# untitled.net
KiCad netlist of a schematic drawn in EAGLE
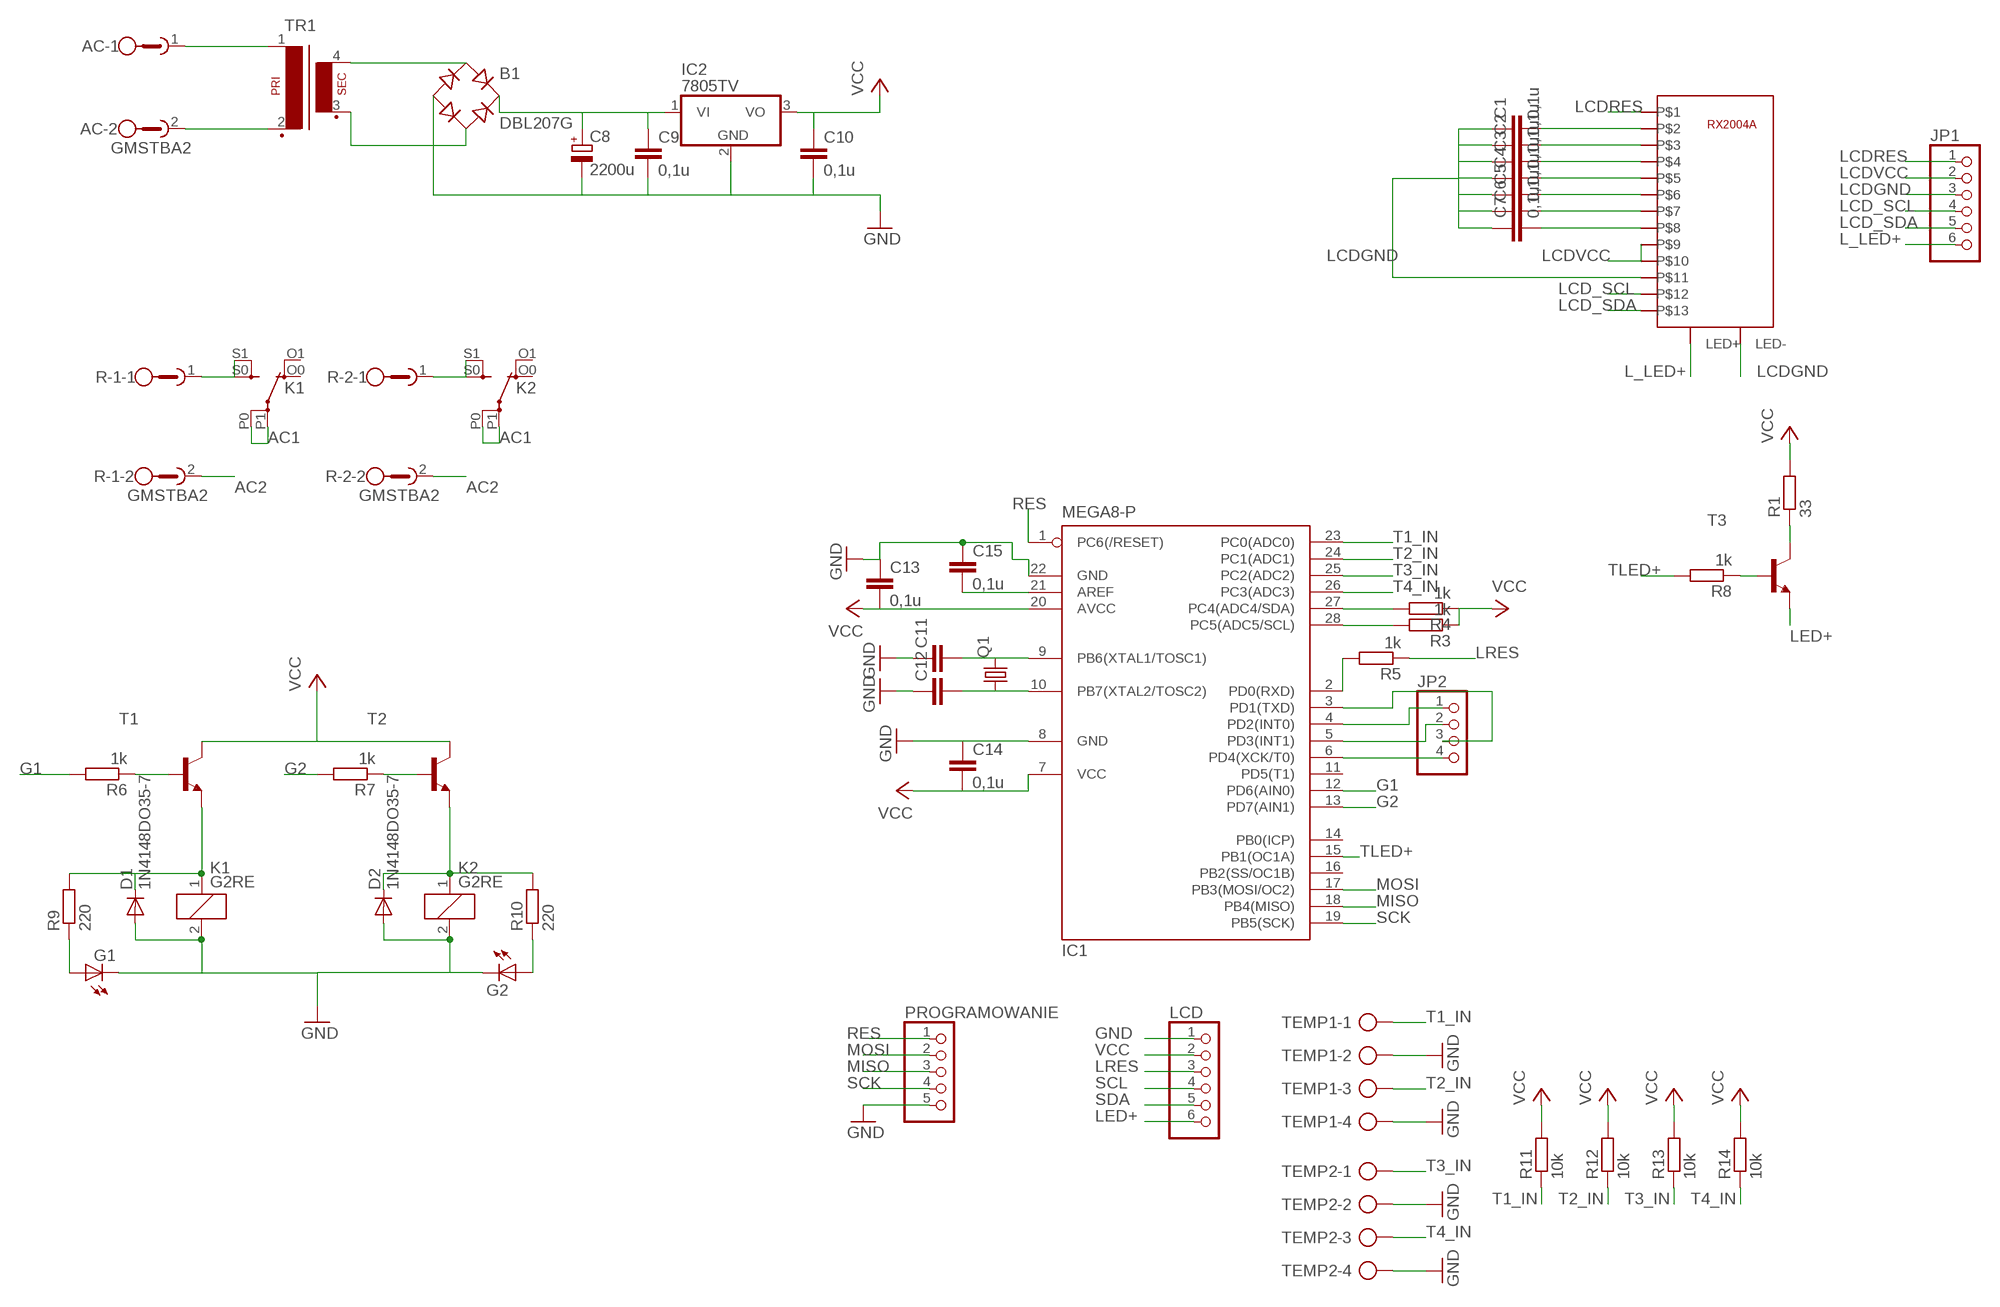
[diagram p0: schematic, sheet 1]

(export (version "E")
  (design (tool "Eeschema 10.0.6"))
  (components
    (comp (ref "AC")
      (value "GMSTBA2")
      (footprint "eagle-import:GMSTBA2")
      (fields (field (name "MF") "FARNELL") (field (name "MPN") "1757242"))
      (libsource (lib "eagle-import") (part "GMSTBA2"))
    )
    (comp (ref "B1")
      (value "DBL207G")
      (footprint "eagle-import:DB")
      (libsource (lib "eagle-import") (part "DB?GL207"))
    )
    (comp (ref "C1")
      (value "0,1u")
      (footprint "eagle-import:C1206K")
      (libsource (lib "eagle-import") (part "C-EUC1206K"))
    )
    (comp (ref "C2")
      (value "0,1u")
      (footprint "eagle-import:C1206K")
      (libsource (lib "eagle-import") (part "C-EUC1206K"))
    )
    (comp (ref "C3")
      (value "0,1u")
      (footprint "eagle-import:C1206K")
      (libsource (lib "eagle-import") (part "C-EUC1206K"))
    )
    (comp (ref "C4")
      (value "0,1u")
      (footprint "eagle-import:C1206K")
      (libsource (lib "eagle-import") (part "C-EUC1206K"))
    )
    (comp (ref "C5")
      (value "0,1u")
      (footprint "eagle-import:C1206K")
      (libsource (lib "eagle-import") (part "C-EUC1206K"))
    )
    (comp (ref "C6")
      (value "0,1u")
      (footprint "eagle-import:C1206K")
      (libsource (lib "eagle-import") (part "C-EUC1206K"))
    )
    (comp (ref "C7")
      (value "0,1u")
      (footprint "eagle-import:C1206K")
      (libsource (lib "eagle-import") (part "C-EUC1206K"))
    )
    (comp (ref "C8")
      (value "2200u")
      (footprint "eagle-import:E7,5-16")
      (libsource (lib "eagle-import") (part "CPOL-EUE7.5-16"))
    )
    (comp (ref "C9")
      (value "0,1u")
      (footprint "eagle-import:C1206K")
      (libsource (lib "eagle-import") (part "C-EUC1206K"))
    )
    (comp (ref "C10")
      (value "0,1u")
      (footprint "eagle-import:C1206K")
      (libsource (lib "eagle-import") (part "C-EUC1206K"))
    )
    (comp (ref "C11")
      (value "C-EU025-024X044")
      (footprint "eagle-import:C025-024X044")
      (libsource (lib "eagle-import") (part "C-EU025-024X044"))
    )
    (comp (ref "C12")
      (value "C-EU025-024X044")
      (footprint "eagle-import:C025-024X044")
      (libsource (lib "eagle-import") (part "C-EU025-024X044"))
    )
    (comp (ref "C13")
      (value "0,1u")
      (footprint "eagle-import:C1206K")
      (libsource (lib "eagle-import") (part "C-EUC1206K"))
    )
    (comp (ref "C14")
      (value "0,1u")
      (footprint "eagle-import:C1206K")
      (libsource (lib "eagle-import") (part "C-EUC1206K"))
    )
    (comp (ref "C15")
      (value "0,1u")
      (footprint "eagle-import:C1206K")
      (libsource (lib "eagle-import") (part "C-EUC1206K"))
    )
    (comp (ref "D1")
      (value "1N4148DO35-7")
      (footprint "eagle-import:DO35-7")
      (libsource (lib "eagle-import") (part "1N4148DO35-7"))
    )
    (comp (ref "D2")
      (value "1N4148DO35-7")
      (footprint "eagle-import:DO35-7")
      (libsource (lib "eagle-import") (part "1N4148DO35-7"))
    )
    (comp (ref "G1")
      (value "LED3MM")
      (footprint "eagle-import:LED3MM")
      (libsource (lib "eagle-import") (part "LED3MM"))
    )
    (comp (ref "G2")
      (value "LED3MM")
      (footprint "eagle-import:LED3MM")
      (libsource (lib "eagle-import") (part "LED3MM"))
    )
    (comp (ref "IC1")
      (value "MEGA8-P")
      (footprint "eagle-import:DIL28-3")
      (libsource (lib "eagle-import") (part "MEGA8-P"))
    )
    (comp (ref "IC2")
      (value "7805TV")
      (footprint "eagle-import:TO220V")
      (libsource (lib "eagle-import") (part "78TV05"))
    )
    (comp (ref "JP1")
      (value "PINHD-1X6/90")
      (footprint "eagle-import:1X06_90")
      (libsource (lib "eagle-import") (part "PINHD-1X6/90"))
    )
    (comp (ref "JP2")
      (value "PINHD-1X4")
      (footprint "eagle-import:1X04")
      (libsource (lib "eagle-import") (part "PINHD-1X4"))
    )
    (comp (ref "K1")
      (value "G2RE")
      (footprint "eagle-import:G2RE")
      (libsource (lib "eagle-import") (part "G2RE"))
    )
    (comp (ref "K2")
      (value "G2RE")
      (footprint "eagle-import:G2RE")
      (libsource (lib "eagle-import") (part "G2RE"))
    )
    (comp (ref "LCD")
      (value "PINHD-1X6")
      (footprint "eagle-import:1X06")
      (libsource (lib "eagle-import") (part "PINHD-1X6"))
    )
    (comp (ref "PROGRAMOWANIE")
      (value "PINHD-1X5")
      (footprint "eagle-import:1X05")
      (libsource (lib "eagle-import") (part "PINHD-1X5"))
    )
    (comp (ref "Q1")
      (value "CRYSTALHC49S")
      (footprint "eagle-import:HC49_S")
      (libsource (lib "eagle-import") (part "CRYSTALHC49S"))
    )
    (comp (ref "R-1")
      (value "GMSTBA2")
      (footprint "eagle-import:GMSTBA2")
      (fields (field (name "MF") "FARNELL") (field (name "MPN") "1757242"))
      (libsource (lib "eagle-import") (part "GMSTBA2"))
    )
    (comp (ref "R-2")
      (value "GMSTBA2")
      (footprint "eagle-import:GMSTBA2")
      (fields (field (name "MF") "FARNELL") (field (name "MPN") "1757242"))
      (libsource (lib "eagle-import") (part "GMSTBA2"))
    )
    (comp (ref "R1")
      (value "33")
      (footprint "eagle-import:0204_7")
      (libsource (lib "eagle-import") (part "R-EU_0204/7"))
    )
    (comp (ref "R3")
      (value "1k")
      (footprint "eagle-import:0204_5")
      (libsource (lib "eagle-import") (part "R-EU_0204/5"))
    )
    (comp (ref "R4")
      (value "1k")
      (footprint "eagle-import:0204_5")
      (libsource (lib "eagle-import") (part "R-EU_0204/5"))
    )
    (comp (ref "R5")
      (value "1k")
      (footprint "eagle-import:0204_7")
      (libsource (lib "eagle-import") (part "R-EU_0204/7"))
    )
    (comp (ref "R6")
      (value "1k")
      (footprint "eagle-import:0204_5")
      (libsource (lib "eagle-import") (part "R-EU_0204/5"))
    )
    (comp (ref "R7")
      (value "1k")
      (footprint "eagle-import:0204_5")
      (libsource (lib "eagle-import") (part "R-EU_0204/5"))
    )
    (comp (ref "R8")
      (value "1k")
      (footprint "eagle-import:0204_5")
      (libsource (lib "eagle-import") (part "R-EU_0204/5"))
    )
    (comp (ref "R9")
      (value "220")
      (footprint "eagle-import:0204_7")
      (libsource (lib "eagle-import") (part "R-EU_0204/7"))
    )
    (comp (ref "R10")
      (value "220")
      (footprint "eagle-import:0204_7")
      (libsource (lib "eagle-import") (part "R-EU_0204/7"))
    )
    (comp (ref "R11")
      (value "10k")
      (footprint "eagle-import:0204_5")
      (libsource (lib "eagle-import") (part "R-EU_0204/5"))
    )
    (comp (ref "R12")
      (value "10k")
      (footprint "eagle-import:0204_5")
      (libsource (lib "eagle-import") (part "R-EU_0204/5"))
    )
    (comp (ref "R13")
      (value "10k")
      (footprint "eagle-import:0204_5")
      (libsource (lib "eagle-import") (part "R-EU_0204/5"))
    )
    (comp (ref "R14")
      (value "10k")
      (footprint "eagle-import:0204_5")
      (libsource (lib "eagle-import") (part "R-EU_0204/5"))
    )
    (comp (ref "T1")
      (value "BC337-NPN-TO92-CBE")
      (footprint "eagle-import:TO92-CBE")
      (libsource (lib "eagle-import") (part "-NPN-TO92-CBEBC337"))
    )
    (comp (ref "T2")
      (value "BC337-NPN-TO92-CBE")
      (footprint "eagle-import:TO92-CBE")
      (libsource (lib "eagle-import") (part "-NPN-TO92-CBEBC337"))
    )
    (comp (ref "T3")
      (value "BC337-NPN-TO92-CBE")
      (footprint "eagle-import:TO92-CBE")
      (libsource (lib "eagle-import") (part "-NPN-TO92-CBEBC337"))
    )
    (comp (ref "TEMP1")
      (value "AK500/4")
      (footprint "eagle-import:AK500_4")
      (libsource (lib "eagle-import") (part "AK500/4"))
    )
    (comp (ref "TEMP2")
      (value "AK500/4")
      (footprint "eagle-import:AK500_4")
      (libsource (lib "eagle-import") (part "AK500/4"))
    )
    (comp (ref "TR1")
      (value "VP31")
      (footprint "eagle-import:VP31")
      (libsource (lib "eagle-import") (part "VP31"))
    )
    (comp (ref "U$1")
      (value "RX2004A")
      (footprint "eagle-import:RX2004A")
      (libsource (lib "eagle-import") (part "RX2004A"))
    )
  )
  (nets
    (net (code "1") (name "/AC1") (class "Default")
      (node (ref "AC") (pin "1") (pinfunction "1_1") (pintype "passive"))
      (node (ref "K1") (pin "P0") (pinfunction "P_P0") (pintype "passive"))
      (node (ref "K1") (pin "P1") (pinfunction "P_P1") (pintype "passive"))
      (node (ref "K2") (pin "P0") (pinfunction "P_P0") (pintype "passive"))
      (node (ref "K2") (pin "P1") (pinfunction "P_P1") (pintype "passive"))
      (node (ref "TR1") (pin "1") (pinfunction "P1_1") (pintype "passive"))
    )
    (net (code "2") (name "/AC2") (class "Default")
      (node (ref "AC") (pin "2") (pinfunction "1_2") (pintype "passive"))
      (node (ref "R-1") (pin "2") (pinfunction "1_2") (pintype "passive"))
      (node (ref "R-2") (pin "2") (pinfunction "1_2") (pintype "passive"))
      (node (ref "TR1") (pin "2") (pinfunction "P2_2") (pintype "passive"))
    )
    (net (code "3") (name "/G1") (class "Default")
      (node (ref "IC1") (pin "12") (pinfunction "PD6(AIN0)_12") (pintype "bidirectional"))
      (node (ref "R6") (pin "2") (pinfunction "2_2") (pintype "passive"))
    )
    (net (code "4") (name "/G2") (class "Default")
      (node (ref "IC1") (pin "13") (pinfunction "PD7(AIN1)_13") (pintype "bidirectional"))
      (node (ref "R7") (pin "2") (pinfunction "2_2") (pintype "passive"))
    )
    (net (code "5") (name "/LCDGND") (class "Default")
      (node (ref "C1") (pin "1") (pinfunction "1_1") (pintype "passive"))
      (node (ref "C2") (pin "1") (pinfunction "1_1") (pintype "passive"))
      (node (ref "C3") (pin "1") (pinfunction "1_1") (pintype "passive"))
      (node (ref "C4") (pin "1") (pinfunction "1_1") (pintype "passive"))
      (node (ref "C5") (pin "1") (pinfunction "1_1") (pintype "passive"))
      (node (ref "C6") (pin "1") (pinfunction "1_1") (pintype "passive"))
      (node (ref "C7") (pin "1") (pinfunction "1_1") (pintype "passive"))
      (node (ref "JP1") (pin "3") (pinfunction "3_3") (pintype "passive"))
      (node (ref "U$1") (pin "LED-") (pinfunction "LED-_LED-") (pintype "bidirectional"))
      (node (ref "U$1") (pin "P$11") (pinfunction "P$11_P$11") (pintype "bidirectional"))
    )
    (net (code "6") (name "/LCDRES") (class "Default")
      (node (ref "JP1") (pin "1") (pinfunction "1_1") (pintype "passive"))
      (node (ref "U$1") (pin "P$1") (pinfunction "P$1_P$1") (pintype "bidirectional"))
    )
    (net (code "7") (name "/LCDVCC") (class "Default")
      (node (ref "JP1") (pin "2") (pinfunction "2_2") (pintype "passive"))
      (node (ref "U$1") (pin "P$10") (pinfunction "P$10_P$10") (pintype "bidirectional"))
      (node (ref "U$1") (pin "P$9") (pinfunction "P$9_P$9") (pintype "bidirectional"))
    )
    (net (code "8") (name "/LCD_SCL") (class "Default")
      (node (ref "JP1") (pin "4") (pinfunction "4_4") (pintype "passive"))
      (node (ref "U$1") (pin "P$12") (pinfunction "P$12_P$12") (pintype "bidirectional"))
    )
    (net (code "9") (name "/LCD_SDA") (class "Default")
      (node (ref "JP1") (pin "5") (pinfunction "5_5") (pintype "passive"))
      (node (ref "U$1") (pin "P$13") (pinfunction "P$13_P$13") (pintype "bidirectional"))
    )
    (net (code "10") (name "/LED+") (class "Default")
      (node (ref "LCD") (pin "6") (pinfunction "6_6") (pintype "passive"))
      (node (ref "T3") (pin "E") (pinfunction "E_E") (pintype "passive"))
    )
    (net (code "11") (name "/LRES") (class "Default")
      (node (ref "LCD") (pin "3") (pinfunction "3_3") (pintype "passive"))
      (node (ref "R5") (pin "1") (pinfunction "1_1") (pintype "passive"))
    )
    (net (code "12") (name "/L_LED+") (class "Default")
      (node (ref "JP1") (pin "6") (pinfunction "6_6") (pintype "passive"))
      (node (ref "U$1") (pin "LED+") (pinfunction "LED+_LED+") (pintype "bidirectional"))
    )
    (net (code "13") (name "/MISO") (class "Default")
      (node (ref "IC1") (pin "18") (pinfunction "PB4(MISO)_18") (pintype "bidirectional"))
      (node (ref "PROGRAMOWANIE") (pin "3") (pinfunction "3_3") (pintype "passive"))
    )
    (net (code "14") (name "/MOSI") (class "Default")
      (node (ref "IC1") (pin "17") (pinfunction "PB3(MOSI/OC2)_17") (pintype "bidirectional"))
      (node (ref "PROGRAMOWANIE") (pin "2") (pinfunction "2_2") (pintype "passive"))
    )
    (net (code "15") (name "/RES") (class "Default")
      (node (ref "IC1") (pin "1") (pinfunction "PC6(/RESET)_1") (pintype "bidirectional"))
      (node (ref "PROGRAMOWANIE") (pin "1") (pinfunction "1_1") (pintype "passive"))
    )
    (net (code "16") (name "/SCK") (class "Default")
      (node (ref "IC1") (pin "19") (pinfunction "PB5(SCK)_19") (pintype "bidirectional"))
      (node (ref "PROGRAMOWANIE") (pin "4") (pinfunction "4_4") (pintype "passive"))
    )
    (net (code "17") (name "/SCL") (class "Default")
      (node (ref "IC1") (pin "28") (pinfunction "PC5(ADC5/SCL)_28") (pintype "bidirectional"))
      (node (ref "LCD") (pin "4") (pinfunction "4_4") (pintype "passive"))
      (node (ref "R3") (pin "2") (pinfunction "2_2") (pintype "passive"))
    )
    (net (code "18") (name "/SDA") (class "Default")
      (node (ref "IC1") (pin "27") (pinfunction "PC4(ADC4/SDA)_27") (pintype "bidirectional"))
      (node (ref "LCD") (pin "5") (pinfunction "5_5") (pintype "passive"))
      (node (ref "R4") (pin "2") (pinfunction "2_2") (pintype "passive"))
    )
    (net (code "19") (name "/T1_IN") (class "Default")
      (node (ref "IC1") (pin "23") (pinfunction "PC0(ADC0)_23") (pintype "bidirectional"))
      (node (ref "R11") (pin "1") (pinfunction "1_1") (pintype "passive"))
      (node (ref "TEMP1") (pin "1") (pinfunction "KL_1") (pintype "passive"))
    )
    (net (code "20") (name "/T2_IN") (class "Default")
      (node (ref "IC1") (pin "24") (pinfunction "PC1(ADC1)_24") (pintype "bidirectional"))
      (node (ref "R12") (pin "1") (pinfunction "1_1") (pintype "passive"))
      (node (ref "TEMP1") (pin "3") (pinfunction "KL_3") (pintype "passive"))
    )
    (net (code "21") (name "/T3_IN") (class "Default")
      (node (ref "IC1") (pin "25") (pinfunction "PC2(ADC2)_25") (pintype "bidirectional"))
      (node (ref "R13") (pin "1") (pinfunction "1_1") (pintype "passive"))
      (node (ref "TEMP2") (pin "1") (pinfunction "KL_1") (pintype "passive"))
    )
    (net (code "22") (name "/T4_IN") (class "Default")
      (node (ref "IC1") (pin "26") (pinfunction "PC3(ADC3)_26") (pintype "bidirectional"))
      (node (ref "R14") (pin "1") (pinfunction "1_1") (pintype "passive"))
      (node (ref "TEMP2") (pin "3") (pinfunction "KL_3") (pintype "passive"))
    )
    (net (code "23") (name "/TLED+") (class "Default")
      (node (ref "IC1") (pin "15") (pinfunction "PB1(OC1A)_15") (pintype "bidirectional"))
      (node (ref "R8") (pin "2") (pinfunction "2_2") (pintype "passive"))
    )
    (net (code "24") (name "GND") (class "Default")
      (node (ref "B1") (pin "-") (pinfunction "-_-") (pintype "passive"))
      (node (ref "C10") (pin "2") (pinfunction "2_2") (pintype "passive"))
      (node (ref "C11") (pin "1") (pinfunction "1_1") (pintype "passive"))
      (node (ref "C12") (pin "1") (pinfunction "1_1") (pintype "passive"))
      (node (ref "C13") (pin "1") (pinfunction "1_1") (pintype "passive"))
      (node (ref "C14") (pin "1") (pinfunction "1_1") (pintype "passive"))
      (node (ref "C15") (pin "1") (pinfunction "1_1") (pintype "passive"))
      (node (ref "C8") (pin "-") (pinfunction "-_-") (pintype "passive"))
      (node (ref "C9") (pin "2") (pinfunction "2_2") (pintype "passive"))
      (node (ref "D1") (pin "A") (pinfunction "A_A") (pintype "passive"))
      (node (ref "D2") (pin "A") (pinfunction "A_A") (pintype "passive"))
      (node (ref "G1") (pin "K") (pinfunction "C_K") (pintype "passive"))
      (node (ref "G2") (pin "K") (pinfunction "C_K") (pintype "passive"))
      (node (ref "IC1") (pin "22") (pinfunction "GND_22") (pintype "power_in"))
      (node (ref "IC1") (pin "8") (pinfunction "GND_8") (pintype "power_in"))
      (node (ref "IC2") (pin "2") (pinfunction "GND_2") (pintype "passive"))
      (node (ref "K1") (pin "2") (pinfunction "2_2") (pintype "passive"))
      (node (ref "K2") (pin "2") (pinfunction "2_2") (pintype "passive"))
      (node (ref "LCD") (pin "1") (pinfunction "1_1") (pintype "passive"))
      (node (ref "PROGRAMOWANIE") (pin "5") (pinfunction "5_5") (pintype "passive"))
      (node (ref "TEMP1") (pin "2") (pinfunction "KL_2") (pintype "passive"))
      (node (ref "TEMP1") (pin "4") (pinfunction "KL_4") (pintype "passive"))
      (node (ref "TEMP2") (pin "2") (pinfunction "KL_2") (pintype "passive"))
      (node (ref "TEMP2") (pin "4") (pinfunction "KL_4") (pintype "passive"))
    )
    (net (code "25") (name "Net-(C1-Pad2)") (class "Default")
      (node (ref "C1") (pin "2") (pinfunction "2_2") (pintype "passive"))
      (node (ref "U$1") (pin "P$2") (pinfunction "P$2_P$2") (pintype "bidirectional"))
    )
    (net (code "26") (name "Net-(C2-Pad2)") (class "Default")
      (node (ref "C2") (pin "2") (pinfunction "2_2") (pintype "passive"))
      (node (ref "U$1") (pin "P$3") (pinfunction "P$3_P$3") (pintype "bidirectional"))
    )
    (net (code "27") (name "Net-(C3-Pad2)") (class "Default")
      (node (ref "C3") (pin "2") (pinfunction "2_2") (pintype "passive"))
      (node (ref "U$1") (pin "P$4") (pinfunction "P$4_P$4") (pintype "bidirectional"))
    )
    (net (code "28") (name "Net-(C4-Pad2)") (class "Default")
      (node (ref "C4") (pin "2") (pinfunction "2_2") (pintype "passive"))
      (node (ref "U$1") (pin "P$5") (pinfunction "P$5_P$5") (pintype "bidirectional"))
    )
    (net (code "29") (name "Net-(C5-Pad2)") (class "Default")
      (node (ref "C5") (pin "2") (pinfunction "2_2") (pintype "passive"))
      (node (ref "U$1") (pin "P$6") (pinfunction "P$6_P$6") (pintype "bidirectional"))
    )
    (net (code "30") (name "Net-(C6-Pad2)") (class "Default")
      (node (ref "C6") (pin "2") (pinfunction "2_2") (pintype "passive"))
      (node (ref "U$1") (pin "P$7") (pinfunction "P$7_P$7") (pintype "bidirectional"))
    )
    (net (code "31") (name "Net-(C7-Pad2)") (class "Default")
      (node (ref "C7") (pin "2") (pinfunction "2_2") (pintype "passive"))
      (node (ref "U$1") (pin "P$8") (pinfunction "P$8_P$8") (pintype "bidirectional"))
    )
    (net (code "32") (name "Net-(D1-PadC)") (class "Default")
      (node (ref "D1") (pin "C") (pinfunction "C_C") (pintype "passive"))
      (node (ref "K1") (pin "1") (pinfunction "1_1") (pintype "passive"))
      (node (ref "R9") (pin "2") (pinfunction "2_2") (pintype "passive"))
      (node (ref "T1") (pin "E") (pinfunction "E_E") (pintype "passive"))
    )
    (net (code "33") (name "Net-(D2-PadC)") (class "Default")
      (node (ref "D2") (pin "C") (pinfunction "C_C") (pintype "passive"))
      (node (ref "K2") (pin "1") (pinfunction "1_1") (pintype "passive"))
      (node (ref "R10") (pin "2") (pinfunction "2_2") (pintype "passive"))
      (node (ref "T2") (pin "E") (pinfunction "E_E") (pintype "passive"))
    )
    (net (code "34") (name "Net-(G1-PadA)") (class "Default")
      (node (ref "G1") (pin "A") (pinfunction "A_A") (pintype "passive"))
      (node (ref "R9") (pin "1") (pinfunction "1_1") (pintype "passive"))
    )
    (net (code "35") (name "Net-(G2-PadA)") (class "Default")
      (node (ref "G2") (pin "A") (pinfunction "A_A") (pintype "passive"))
      (node (ref "R10") (pin "1") (pinfunction "1_1") (pintype "passive"))
    )
    (net (code "36") (name "Net-(IC1-AREF)") (class "Default")
      (node (ref "C15") (pin "2") (pinfunction "2_2") (pintype "passive"))
      (node (ref "IC1") (pin "21") (pinfunction "AREF_21") (pintype "passive"))
    )
    (net (code "37") (name "Net-(IC1-PB6(XTAL1{slash}TOSC1))") (class "Default")
      (node (ref "C11") (pin "2") (pinfunction "2_2") (pintype "passive"))
      (node (ref "IC1") (pin "9") (pinfunction "PB6(XTAL1/TOSC1)_9") (pintype "bidirectional"))
      (node (ref "Q1") (pin "2") (pinfunction "2_2") (pintype "passive"))
    )
    (net (code "38") (name "Net-(IC1-PB7(XTAL2{slash}TOSC2))") (class "Default")
      (node (ref "C12") (pin "2") (pinfunction "2_2") (pintype "passive"))
      (node (ref "IC1") (pin "10") (pinfunction "PB7(XTAL2/TOSC2)_10") (pintype "bidirectional"))
      (node (ref "Q1") (pin "1") (pinfunction "1_1") (pintype "passive"))
    )
    (net (code "39") (name "Net-(IC1-PD0(RXD))") (class "Default")
      (node (ref "IC1") (pin "2") (pinfunction "PD0(RXD)_2") (pintype "bidirectional"))
      (node (ref "R5") (pin "2") (pinfunction "2_2") (pintype "passive"))
    )
    (net (code "40") (name "Net-(IC1-PD1(TXD))") (class "Default")
      (node (ref "IC1") (pin "3") (pinfunction "PD1(TXD)_3") (pintype "bidirectional"))
      (node (ref "JP2") (pin "3") (pinfunction "3_3") (pintype "passive"))
    )
    (net (code "41") (name "Net-(IC1-PD2(INT0))") (class "Default")
      (node (ref "IC1") (pin "4") (pinfunction "PD2(INT0)_4") (pintype "bidirectional"))
      (node (ref "JP2") (pin "1") (pinfunction "1_1") (pintype "passive"))
    )
    (net (code "42") (name "Net-(IC1-PD3(INT1))") (class "Default")
      (node (ref "IC1") (pin "5") (pinfunction "PD3(INT1)_5") (pintype "bidirectional"))
      (node (ref "JP2") (pin "2") (pinfunction "2_2") (pintype "passive"))
    )
    (net (code "43") (name "Net-(IC1-PD4(XCK{slash}T0))") (class "Default")
      (node (ref "IC1") (pin "6") (pinfunction "PD4(XCK/T0)_6") (pintype "bidirectional"))
      (node (ref "JP2") (pin "4") (pinfunction "4_4") (pintype "passive"))
    )
    (net (code "44") (name "Net-(IC2-VI)") (class "Default")
      (node (ref "B1") (pin "+") (pinfunction "+_+") (pintype "passive"))
      (node (ref "C8") (pin "+") (pinfunction "+_+") (pintype "passive"))
      (node (ref "C9") (pin "1") (pinfunction "1_1") (pintype "passive"))
      (node (ref "IC2") (pin "1") (pinfunction "VI_1") (pintype "input"))
    )
    (net (code "45") (name "Net-(K1B-S-PadS0)") (class "Default")
      (node (ref "K1") (pin "S0") (pinfunction "S_S0") (pintype "passive"))
      (node (ref "K1") (pin "S1") (pinfunction "S_S1") (pintype "passive"))
      (node (ref "R-1") (pin "1") (pinfunction "1_1") (pintype "passive"))
    )
    (net (code "46") (name "Net-(K2B-S-PadS0)") (class "Default")
      (node (ref "K2") (pin "S0") (pinfunction "S_S0") (pintype "passive"))
      (node (ref "K2") (pin "S1") (pinfunction "S_S1") (pintype "passive"))
      (node (ref "R-2") (pin "1") (pinfunction "1_1") (pintype "passive"))
    )
    (net (code "47") (name "Net-(R1-Pad1)") (class "Default")
      (node (ref "R1") (pin "1") (pinfunction "1_1") (pintype "passive"))
      (node (ref "T3") (pin "C") (pinfunction "C_C") (pintype "passive"))
    )
    (net (code "48") (name "Net-(R6-Pad1)") (class "Default")
      (node (ref "R6") (pin "1") (pinfunction "1_1") (pintype "passive"))
      (node (ref "T1") (pin "B") (pinfunction "B_B") (pintype "passive"))
    )
    (net (code "49") (name "Net-(R7-Pad1)") (class "Default")
      (node (ref "R7") (pin "1") (pinfunction "1_1") (pintype "passive"))
      (node (ref "T2") (pin "B") (pinfunction "B_B") (pintype "passive"))
    )
    (net (code "50") (name "Net-(R8-Pad1)") (class "Default")
      (node (ref "R8") (pin "1") (pinfunction "1_1") (pintype "passive"))
      (node (ref "T3") (pin "B") (pinfunction "B_B") (pintype "passive"))
    )
    (net (code "51") (name "Net-(TR1-S3)") (class "Default")
      (node (ref "B1") (pin "AC2") (pinfunction "AC2_AC2") (pintype "passive"))
      (node (ref "TR1") (pin "3") (pinfunction "S3_3") (pintype "passive"))
    )
    (net (code "52") (name "Net-(TR1-S4)") (class "Default")
      (node (ref "B1") (pin "AC1") (pinfunction "AC1_AC1") (pintype "passive"))
      (node (ref "TR1") (pin "4") (pinfunction "S4_4") (pintype "passive"))
    )
    (net (code "53") (name "VCC") (class "Default")
      (node (ref "C10") (pin "1") (pinfunction "1_1") (pintype "passive"))
      (node (ref "C13") (pin "2") (pinfunction "2_2") (pintype "passive"))
      (node (ref "C14") (pin "2") (pinfunction "2_2") (pintype "passive"))
      (node (ref "IC1") (pin "20") (pinfunction "AVCC_20") (pintype "power_in"))
      (node (ref "IC1") (pin "7") (pinfunction "VCC_7") (pintype "power_in"))
      (node (ref "IC2") (pin "3") (pinfunction "VO_3") (pintype "passive"))
      (node (ref "LCD") (pin "2") (pinfunction "2_2") (pintype "passive"))
      (node (ref "R1") (pin "2") (pinfunction "2_2") (pintype "passive"))
      (node (ref "R11") (pin "2") (pinfunction "2_2") (pintype "passive"))
      (node (ref "R12") (pin "2") (pinfunction "2_2") (pintype "passive"))
      (node (ref "R13") (pin "2") (pinfunction "2_2") (pintype "passive"))
      (node (ref "R14") (pin "2") (pinfunction "2_2") (pintype "passive"))
      (node (ref "R3") (pin "1") (pinfunction "1_1") (pintype "passive"))
      (node (ref "R4") (pin "1") (pinfunction "1_1") (pintype "passive"))
      (node (ref "T1") (pin "C") (pinfunction "C_C") (pintype "passive"))
      (node (ref "T2") (pin "C") (pinfunction "C_C") (pintype "passive"))
    )
    (net (code "54") (name "unconnected-(IC1-PB0(ICP)-Pad14)") (class "Default")
      (node (ref "IC1") (pin "14") (pinfunction "PB0(ICP)_14") (pintype "bidirectional"))
    )
    (net (code "55") (name "unconnected-(IC1-PB2(SS{slash}OC1B)-Pad16)") (class "Default")
      (node (ref "IC1") (pin "16") (pinfunction "PB2(SS/OC1B)_16") (pintype "bidirectional"))
    )
    (net (code "56") (name "unconnected-(IC1-PD5(T1)-Pad11)") (class "Default")
      (node (ref "IC1") (pin "11") (pinfunction "PD5(T1)_11") (pintype "bidirectional"))
    )
    (net (code "57") (name "unconnected-(K1B-O-PadO0)") (class "Default")
      (node (ref "K1") (pin "O0") (pinfunction "O_O0") (pintype "passive"))
    )
    (net (code "58") (name "unconnected-(K1B-O-PadO1)") (class "Default")
      (node (ref "K1") (pin "O1") (pinfunction "O_O1") (pintype "passive"))
    )
    (net (code "59") (name "unconnected-(K2B-O-PadO0)") (class "Default")
      (node (ref "K2") (pin "O0") (pinfunction "O_O0") (pintype "passive"))
    )
    (net (code "60") (name "unconnected-(K2B-O-PadO1)") (class "Default")
      (node (ref "K2") (pin "O1") (pinfunction "O_O1") (pintype "passive"))
    )
  )
)
